# MR_UartConnector.net
KiCad netlist of a schematic drawn in Altium Designer
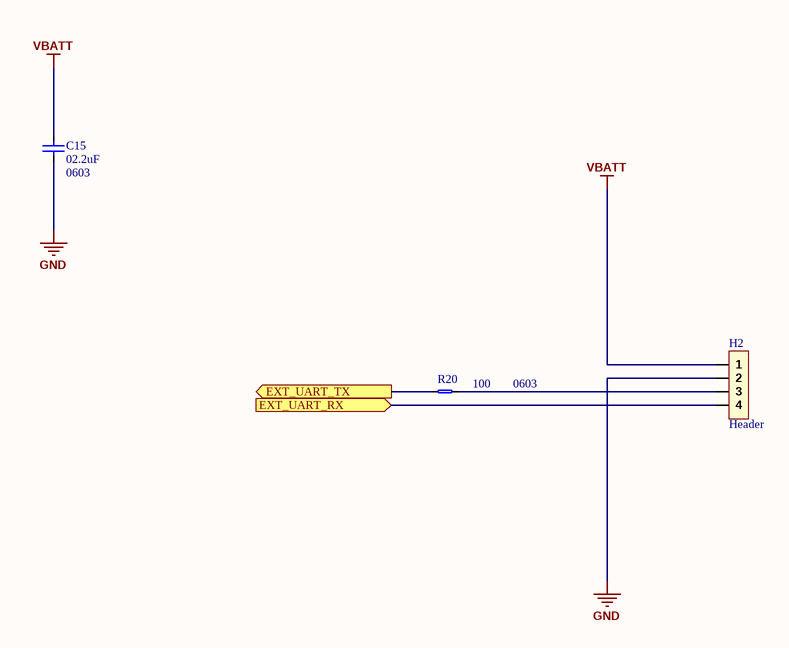
[diagram p0: MR_UartConnector.SchDoc]

(export (version "E")
  (design (tool "Eeschema 10.0.6"))
  (components
    (comp (ref "C15")
      (value "02.2uF")
      (footprint "0603_CAP_LD")
      (description "Ceramic Capacitor")
      (fields (field (name "PACKAGE") "0603") (field (name "Comment") "CerCap"))
      (libsource (lib "MiniRobot") (part "CerCap"))
    )
    (comp (ref "H2")
      (value "Header")
      (footprint "HE14 1x4 Straight")
      (description "Header 4x1 PIns")
      (libsource (lib "MiniRobot") (part "Header_4x1"))
    )
    (comp (ref "R20")
      (value "100")
      (footprint "0603_RES_LD")
      (description "Resistor")
      (fields (field (name "PACKAGE") "0603"))
      (libsource (lib "MiniRobot") (part "Resistor"))
    )
  )
  (nets
    (net (code "1") (name "/EXT_UART_RX") (class "Default")
      (node (ref "H2") (pin "4") (pinfunction "4_4") (pintype "passive"))
    )
    (net (code "2") (name "/EXT_UART_TX") (class "Default")
      (node (ref "R20") (pin "1") (pinfunction "1_1") (pintype "passive"))
    )
    (net (code "3") (name "GND") (class "Default")
      (node (ref "C15") (pin "1") (pinfunction "1_1") (pintype "passive"))
      (node (ref "H2") (pin "2") (pinfunction "2_2") (pintype "passive"))
    )
    (net (code "4") (name "Net-(H2-Pad3)") (class "Default")
      (node (ref "H2") (pin "3") (pinfunction "3_3") (pintype "passive"))
      (node (ref "R20") (pin "2") (pinfunction "2_2") (pintype "passive"))
    )
    (net (code "5") (name "VBATT") (class "Default")
      (node (ref "C15") (pin "2") (pinfunction "2_2") (pintype "passive"))
      (node (ref "H2") (pin "1") (pinfunction "1_1") (pintype "passive"))
    )
  )
)
